# Sonar_Power_Schematic_LT1962_5_33.net
KiCad netlist of a schematic drawn in EAGLE
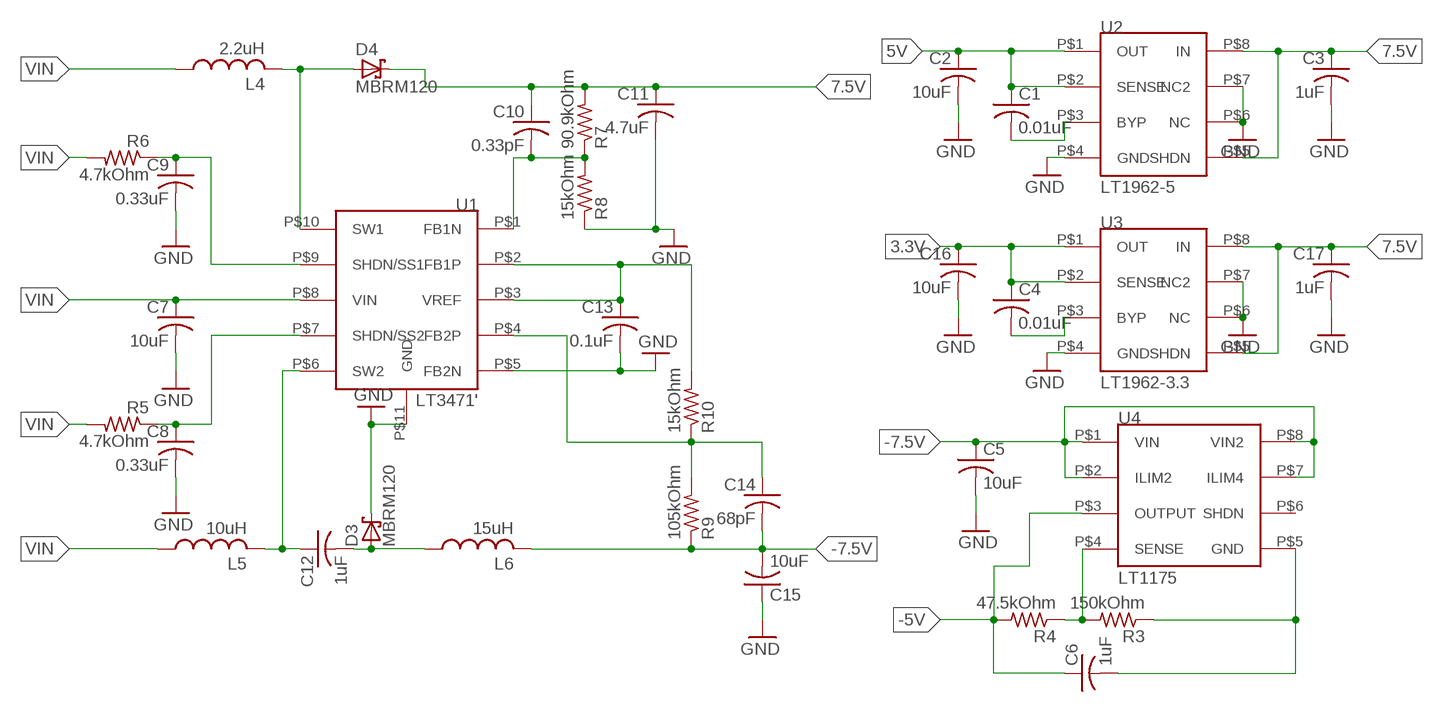
[diagram p0: schematic, sheet 1]

(export (version "E")
  (design (tool "Eeschema 10.0.6"))
  (components
    (comp (ref "C1")
      (value "0.01uF")
      (footprint "eagle-import:C0603")
      (libsource (lib "eagle-import") (part "C-USC0603"))
    )
    (comp (ref "C2")
      (value "10uF")
      (footprint "eagle-import:C0603")
      (libsource (lib "eagle-import") (part "C-USC0603"))
    )
    (comp (ref "C3")
      (value "1uF")
      (footprint "eagle-import:C0603")
      (libsource (lib "eagle-import") (part "C-USC0603"))
    )
    (comp (ref "C4")
      (value "0.01uF")
      (footprint "eagle-import:C0603")
      (libsource (lib "eagle-import") (part "C-USC0603"))
    )
    (comp (ref "C5")
      (value "10uF")
      (footprint "eagle-import:C0603")
      (libsource (lib "eagle-import") (part "C-USC0603"))
    )
    (comp (ref "C6")
      (value "1uF")
      (footprint "eagle-import:C0603")
      (libsource (lib "eagle-import") (part "C-USC0603"))
    )
    (comp (ref "C7")
      (value "10uF")
      (footprint "eagle-import:C0603")
      (libsource (lib "eagle-import") (part "C-USC0603"))
    )
    (comp (ref "C8")
      (value "0.33uF")
      (footprint "eagle-import:C0603")
      (libsource (lib "eagle-import") (part "C-USC0603"))
    )
    (comp (ref "C9")
      (value "0.33uF")
      (footprint "eagle-import:C0603")
      (libsource (lib "eagle-import") (part "C-USC0603"))
    )
    (comp (ref "C10")
      (value "0.33pF")
      (footprint "eagle-import:C0603")
      (libsource (lib "eagle-import") (part "C-USC0603"))
    )
    (comp (ref "C11")
      (value "4.7uF")
      (footprint "eagle-import:C0603")
      (libsource (lib "eagle-import") (part "C-USC0603"))
    )
    (comp (ref "C12")
      (value "1uF")
      (footprint "eagle-import:C0603")
      (libsource (lib "eagle-import") (part "C-USC0603"))
    )
    (comp (ref "C13")
      (value "0.1uF")
      (footprint "eagle-import:C0603")
      (libsource (lib "eagle-import") (part "C-USC0603"))
    )
    (comp (ref "C14")
      (value "68pF")
      (footprint "eagle-import:C0603")
      (libsource (lib "eagle-import") (part "C-USC0603"))
    )
    (comp (ref "C15")
      (value "10uF")
      (footprint "eagle-import:C0603")
      (libsource (lib "eagle-import") (part "C-USC0603"))
    )
    (comp (ref "C16")
      (value "10uF")
      (footprint "eagle-import:C0603")
      (libsource (lib "eagle-import") (part "C-USC0603"))
    )
    (comp (ref "C17")
      (value "1uF")
      (footprint "eagle-import:C0603")
      (libsource (lib "eagle-import") (part "C-USC0603"))
    )
    (comp (ref "D3")
      (value "MBRM120")
      (footprint "eagle-import:DO-216AA")
      (libsource (lib "eagle-import") (part "MBRM120"))
    )
    (comp (ref "D4")
      (value "MBRM120")
      (footprint "eagle-import:DO-216AA")
      (libsource (lib "eagle-import") (part "MBRM120"))
    )
    (comp (ref "L4")
      (value "2.2uH")
      (footprint "eagle-import:NS4.9X4.9")
      (libsource (lib "eagle-import") (part "LQH5BPN2R2N38L"))
    )
    (comp (ref "L5")
      (value "10uH")
      (footprint "eagle-import:NS5X5")
      (libsource (lib "eagle-import") (part "VLS5045EX-100M2"))
    )
    (comp (ref "L6")
      (value "15uH")
      (footprint "eagle-import:NS5X5")
      (libsource (lib "eagle-import") (part "VLS5045EX-150M-CA1"))
    )
    (comp (ref "R3")
      (value "150kOhm")
      (footprint "eagle-import:R0603")
      (libsource (lib "eagle-import") (part "R-US_R0603"))
    )
    (comp (ref "R4")
      (value "47.5kOhm")
      (footprint "eagle-import:R0603")
      (libsource (lib "eagle-import") (part "R-US_R0603"))
    )
    (comp (ref "R5")
      (value "4.7kOhm")
      (footprint "eagle-import:R0603")
      (libsource (lib "eagle-import") (part "R-US_R0603"))
    )
    (comp (ref "R6")
      (value "4.7kOhm")
      (footprint "eagle-import:R0603")
      (libsource (lib "eagle-import") (part "R-US_R0603"))
    )
    (comp (ref "R7")
      (value "90.9kOhm")
      (footprint "eagle-import:R0603")
      (libsource (lib "eagle-import") (part "R-US_R0603"))
    )
    (comp (ref "R8")
      (value "15kOhm")
      (footprint "eagle-import:R0603")
      (libsource (lib "eagle-import") (part "R-US_R0603"))
    )
    (comp (ref "R9")
      (value "105kOhm")
      (footprint "eagle-import:R0603")
      (libsource (lib "eagle-import") (part "R-US_R0603"))
    )
    (comp (ref "R10")
      (value "15kOhm")
      (footprint "eagle-import:R0603")
      (libsource (lib "eagle-import") (part "R-US_R0603"))
    )
    (comp (ref "U1")
      (value "LT3471'")
      (footprint "eagle-import:10-WFDFN")
      (libsource (lib "eagle-import") (part "LT3471'"))
    )
    (comp (ref "U2")
      (value "LT1962-5")
      (footprint "eagle-import:8-MSOP")
      (libsource (lib "eagle-import") (part "LT1962-5"))
    )
    (comp (ref "U3")
      (value "LT1962-3.3")
      (footprint "eagle-import:8-MSOP")
      (libsource (lib "eagle-import") (part "LT1962-3.3"))
    )
    (comp (ref "U4")
      (value "LT1175")
      (footprint "eagle-import:8-SOIC")
      (libsource (lib "eagle-import") (part "LT1175"))
    )
  )
  (nets
    (net (code "1") (name "-5V") (class "Default")
      (node (ref "C6") (pin "1") (pinfunction "1_1") (pintype "passive"))
      (node (ref "R4") (pin "2") (pinfunction "2_2") (pintype "passive"))
      (node (ref "U4") (pin "P$3") (pinfunction "OUTPUT_P$3") (pintype "bidirectional"))
    )
    (net (code "2") (name "-7.5V") (class "Default")
      (node (ref "C14") (pin "2") (pinfunction "2_2") (pintype "passive"))
      (node (ref "C15") (pin "2") (pinfunction "2_2") (pintype "passive"))
      (node (ref "C5") (pin "1") (pinfunction "1_1") (pintype "passive"))
      (node (ref "L6") (pin "P$2") (pinfunction "2_P$2") (pintype "passive"))
      (node (ref "R9") (pin "1") (pinfunction "1_1") (pintype "passive"))
      (node (ref "U4") (pin "P$1") (pinfunction "VIN_P$1") (pintype "power_in"))
      (node (ref "U4") (pin "P$2") (pinfunction "ILIM2_P$2") (pintype "bidirectional"))
      (node (ref "U4") (pin "P$7") (pinfunction "ILIM4_P$7") (pintype "bidirectional"))
      (node (ref "U4") (pin "P$8") (pinfunction "VIN2_P$8") (pintype "power_in"))
    )
    (net (code "3") (name "3.3V") (class "Default")
      (node (ref "C16") (pin "1") (pinfunction "1_1") (pintype "passive"))
      (node (ref "C4") (pin "1") (pinfunction "1_1") (pintype "passive"))
      (node (ref "U3") (pin "P$1") (pinfunction "OUT_P$1") (pintype "bidirectional"))
      (node (ref "U3") (pin "P$2") (pinfunction "SENSE_P$2") (pintype "bidirectional"))
    )
    (net (code "4") (name "5V") (class "Default")
      (node (ref "C1") (pin "1") (pinfunction "1_1") (pintype "passive"))
      (node (ref "C2") (pin "1") (pinfunction "1_1") (pintype "passive"))
      (node (ref "U2") (pin "P$1") (pinfunction "OUT_P$1") (pintype "bidirectional"))
      (node (ref "U2") (pin "P$2") (pinfunction "SENSE_P$2") (pintype "bidirectional"))
    )
    (net (code "5") (name "7.5V") (class "Default")
      (node (ref "C10") (pin "1") (pinfunction "1_1") (pintype "passive"))
      (node (ref "C11") (pin "1") (pinfunction "1_1") (pintype "passive"))
      (node (ref "C17") (pin "1") (pinfunction "1_1") (pintype "passive"))
      (node (ref "C3") (pin "1") (pinfunction "1_1") (pintype "passive"))
      (node (ref "D4") (pin "P$1") (pinfunction "C_P$1") (pintype "passive"))
      (node (ref "R7") (pin "2") (pinfunction "2_2") (pintype "passive"))
      (node (ref "U2") (pin "P$5") (pinfunction "SHDN_P$5") (pintype "bidirectional"))
      (node (ref "U2") (pin "P$8") (pinfunction "IN_P$8") (pintype "bidirectional"))
      (node (ref "U3") (pin "P$5") (pinfunction "SHDN_P$5") (pintype "bidirectional"))
      (node (ref "U3") (pin "P$8") (pinfunction "IN_P$8") (pintype "bidirectional"))
    )
    (net (code "6") (name "GND") (class "Default")
      (node (ref "C11") (pin "2") (pinfunction "2_2") (pintype "passive"))
      (node (ref "C13") (pin "2") (pinfunction "2_2") (pintype "passive"))
      (node (ref "C15") (pin "1") (pinfunction "1_1") (pintype "passive"))
      (node (ref "C16") (pin "2") (pinfunction "2_2") (pintype "passive"))
      (node (ref "C17") (pin "2") (pinfunction "2_2") (pintype "passive"))
      (node (ref "C2") (pin "2") (pinfunction "2_2") (pintype "passive"))
      (node (ref "C3") (pin "2") (pinfunction "2_2") (pintype "passive"))
      (node (ref "C5") (pin "2") (pinfunction "2_2") (pintype "passive"))
      (node (ref "C7") (pin "2") (pinfunction "2_2") (pintype "passive"))
      (node (ref "C8") (pin "2") (pinfunction "2_2") (pintype "passive"))
      (node (ref "C9") (pin "2") (pinfunction "2_2") (pintype "passive"))
      (node (ref "D3") (pin "P$1") (pinfunction "C_P$1") (pintype "passive"))
      (node (ref "R8") (pin "1") (pinfunction "1_1") (pintype "passive"))
      (node (ref "U1") (pin "P$11") (pinfunction "GND_P$11") (pintype "power_in"))
      (node (ref "U1") (pin "P$5") (pinfunction "FB2N_P$5") (pintype "bidirectional"))
      (node (ref "U2") (pin "P$4") (pinfunction "GND_P$4") (pintype "bidirectional"))
      (node (ref "U2") (pin "P$6") (pinfunction "NC_P$6") (pintype "bidirectional"))
      (node (ref "U2") (pin "P$7") (pinfunction "NC2_P$7") (pintype "bidirectional"))
      (node (ref "U3") (pin "P$4") (pinfunction "GND_P$4") (pintype "bidirectional"))
      (node (ref "U3") (pin "P$6") (pinfunction "NC_P$6") (pintype "bidirectional"))
      (node (ref "U3") (pin "P$7") (pinfunction "NC2_P$7") (pintype "bidirectional"))
    )
    (net (code "7") (name "Net-(D3-A)") (class "Default")
      (node (ref "C12") (pin "2") (pinfunction "2_2") (pintype "passive"))
      (node (ref "D3") (pin "P$2") (pinfunction "A_P$2") (pintype "passive"))
      (node (ref "L6") (pin "P$1") (pinfunction "1_P$1") (pintype "passive"))
    )
    (net (code "8") (name "Net-(D4-A)") (class "Default")
      (node (ref "D4") (pin "P$2") (pinfunction "A_P$2") (pintype "passive"))
      (node (ref "L4") (pin "P$2") (pinfunction "2_P$2") (pintype "passive"))
      (node (ref "U1") (pin "P$10") (pinfunction "SW1_P$10") (pintype "bidirectional"))
    )
    (net (code "9") (name "Net-(L5-2)") (class "Default")
      (node (ref "C12") (pin "1") (pinfunction "1_1") (pintype "passive"))
      (node (ref "L5") (pin "P$2") (pinfunction "2_P$2") (pintype "passive"))
      (node (ref "U1") (pin "P$6") (pinfunction "SW2_P$6") (pintype "bidirectional"))
    )
    (net (code "10") (name "Net-(U1-FB1N)") (class "Default")
      (node (ref "C10") (pin "2") (pinfunction "2_2") (pintype "passive"))
      (node (ref "R7") (pin "1") (pinfunction "1_1") (pintype "passive"))
      (node (ref "R8") (pin "2") (pinfunction "2_2") (pintype "passive"))
      (node (ref "U1") (pin "P$1") (pinfunction "FB1N_P$1") (pintype "bidirectional"))
    )
    (net (code "11") (name "Net-(U1-FB1P)") (class "Default")
      (node (ref "C13") (pin "1") (pinfunction "1_1") (pintype "passive"))
      (node (ref "R10") (pin "2") (pinfunction "2_2") (pintype "passive"))
      (node (ref "U1") (pin "P$2") (pinfunction "FB1P_P$2") (pintype "bidirectional"))
      (node (ref "U1") (pin "P$3") (pinfunction "VREF_P$3") (pintype "power_in"))
    )
    (net (code "12") (name "Net-(U1-FB2P)") (class "Default")
      (node (ref "C14") (pin "1") (pinfunction "1_1") (pintype "passive"))
      (node (ref "R10") (pin "1") (pinfunction "1_1") (pintype "passive"))
      (node (ref "R9") (pin "2") (pinfunction "2_2") (pintype "passive"))
      (node (ref "U1") (pin "P$4") (pinfunction "FB2P_P$4") (pintype "bidirectional"))
    )
    (net (code "13") (name "Net-(U1-SHDN{slash}SS1)") (class "Default")
      (node (ref "C9") (pin "1") (pinfunction "1_1") (pintype "passive"))
      (node (ref "R6") (pin "1") (pinfunction "1_1") (pintype "passive"))
      (node (ref "U1") (pin "P$9") (pinfunction "SHDN/SS1_P$9") (pintype "bidirectional"))
    )
    (net (code "14") (name "Net-(U1-SHDN{slash}SS2)") (class "Default")
      (node (ref "C8") (pin "1") (pinfunction "1_1") (pintype "passive"))
      (node (ref "R5") (pin "1") (pinfunction "1_1") (pintype "passive"))
      (node (ref "U1") (pin "P$7") (pinfunction "SHDN/SS2_P$7") (pintype "bidirectional"))
    )
    (net (code "15") (name "Net-(U2-BYP)") (class "Default")
      (node (ref "C1") (pin "2") (pinfunction "2_2") (pintype "passive"))
      (node (ref "U2") (pin "P$3") (pinfunction "BYP_P$3") (pintype "bidirectional"))
    )
    (net (code "16") (name "Net-(U3-BYP)") (class "Default")
      (node (ref "C4") (pin "2") (pinfunction "2_2") (pintype "passive"))
      (node (ref "U3") (pin "P$3") (pinfunction "BYP_P$3") (pintype "bidirectional"))
    )
    (net (code "17") (name "Net-(U4-GND)") (class "Default")
      (node (ref "C6") (pin "2") (pinfunction "2_2") (pintype "passive"))
      (node (ref "R3") (pin "1") (pinfunction "1_1") (pintype "passive"))
      (node (ref "U4") (pin "P$5") (pinfunction "GND_P$5") (pintype "power_in"))
    )
    (net (code "18") (name "Net-(U4-SENSE)") (class "Default")
      (node (ref "R3") (pin "2") (pinfunction "2_2") (pintype "passive"))
      (node (ref "R4") (pin "1") (pinfunction "1_1") (pintype "passive"))
      (node (ref "U4") (pin "P$4") (pinfunction "SENSE_P$4") (pintype "bidirectional"))
    )
    (net (code "19") (name "VIN") (class "Default")
      (node (ref "C7") (pin "1") (pinfunction "1_1") (pintype "passive"))
      (node (ref "L4") (pin "P$1") (pinfunction "1_P$1") (pintype "passive"))
      (node (ref "L5") (pin "P$1") (pinfunction "1_P$1") (pintype "passive"))
      (node (ref "R5") (pin "2") (pinfunction "2_2") (pintype "passive"))
      (node (ref "R6") (pin "2") (pinfunction "2_2") (pintype "passive"))
      (node (ref "U1") (pin "P$8") (pinfunction "VIN_P$8") (pintype "power_in"))
    )
    (net (code "20") (name "unconnected-(U4-SHDN-PadP$6)") (class "Default")
      (node (ref "U4") (pin "P$6") (pinfunction "SHDN_P$6") (pintype "bidirectional"))
    )
  )
)
